# ArduinoStandaloneUsbSwitch-4Port.net
KiCad netlist of a schematic drawn in EAGLE
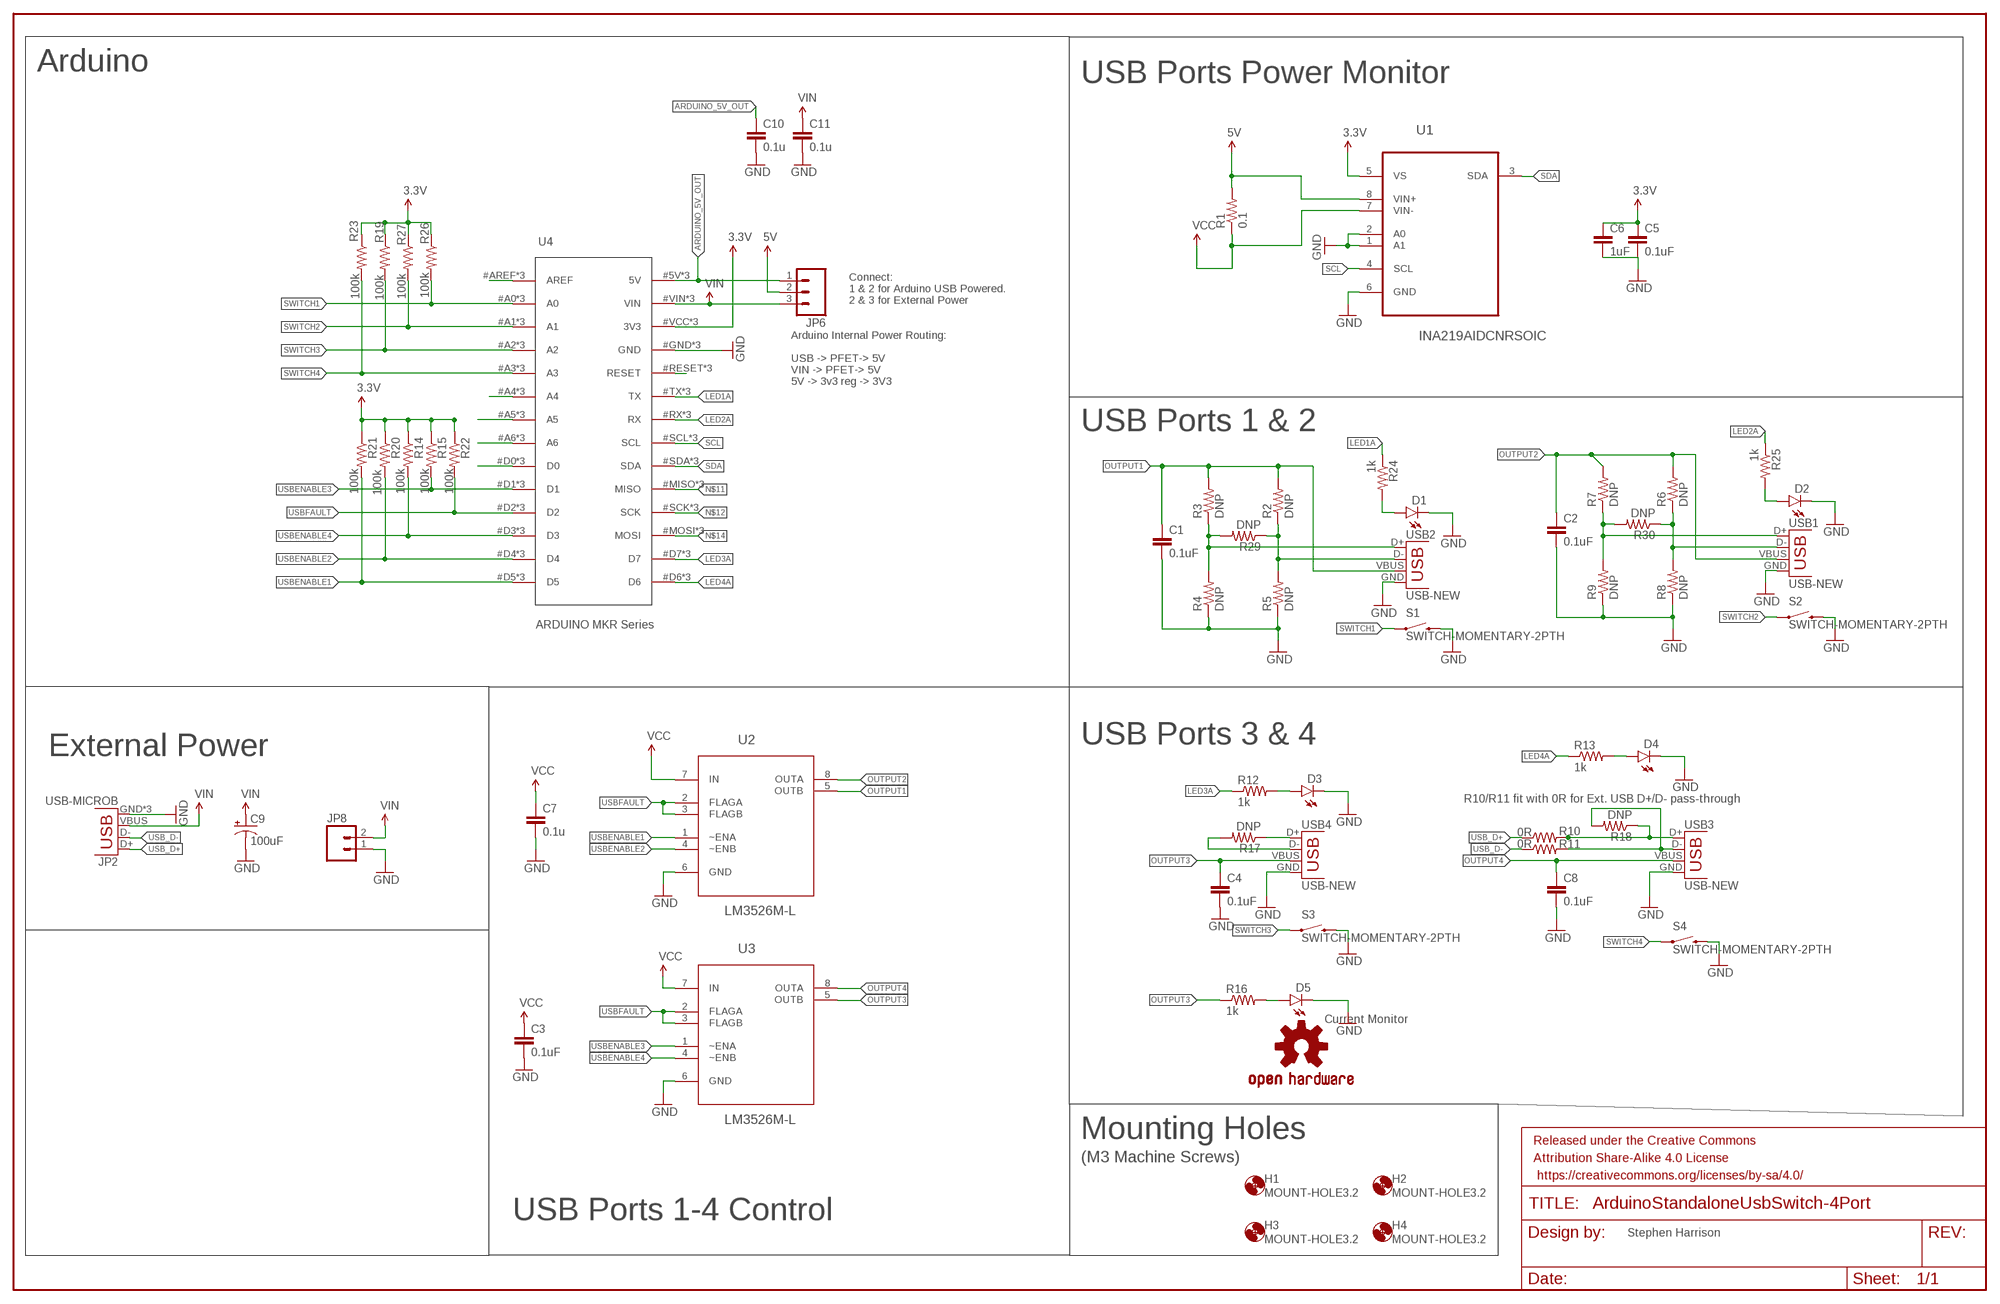
[diagram p0: schematic, sheet 1]

(export (version "E")
  (design (tool "Eeschema 10.0.6"))
  (components
    (comp (ref "C1")
      (value "0.1uF")
      (footprint "eagle-import:0805")
      (libsource (lib "eagle-import") (part "CAP0805"))
    )
    (comp (ref "C2")
      (value "0.1uF")
      (footprint "eagle-import:0805")
      (libsource (lib "eagle-import") (part "CAP0805"))
    )
    (comp (ref "C3")
      (value "0.1uF")
      (footprint "eagle-import:0805")
      (libsource (lib "eagle-import") (part "CAP0805"))
    )
    (comp (ref "C4")
      (value "0.1uF")
      (footprint "eagle-import:0805")
      (libsource (lib "eagle-import") (part "CAP0805"))
    )
    (comp (ref "C5")
      (value "0.1uF")
      (footprint "eagle-import:0805")
      (libsource (lib "eagle-import") (part "CAP0805"))
    )
    (comp (ref "C6")
      (value "1uF")
      (footprint "eagle-import:0805")
      (libsource (lib "eagle-import") (part "CAP0805"))
    )
    (comp (ref "C7")
      (value "0.1u")
      (footprint "eagle-import:0805")
      (libsource (lib "eagle-import") (part "CAP0805"))
    )
    (comp (ref "C8")
      (value "0.1uF")
      (footprint "eagle-import:0805")
      (libsource (lib "eagle-import") (part "CAP0805"))
    )
    (comp (ref "C9")
      (value "100uF")
      (footprint "eagle-import:EIA7343")
      (libsource (lib "eagle-import") (part "100UF-10V-10%(TANT)"))
    )
    (comp (ref "C10")
      (value "0.1u")
      (footprint "eagle-import:0805")
      (libsource (lib "eagle-import") (part "CAP0805"))
    )
    (comp (ref "C11")
      (value "0.1u")
      (footprint "eagle-import:0805")
      (libsource (lib "eagle-import") (part "CAP0805"))
    )
    (comp (ref "D1")
      (value "LED3MM")
      (footprint "eagle-import:LED3MM")
      (libsource (lib "eagle-import") (part "LED3MM"))
    )
    (comp (ref "D2")
      (value "LED3MM")
      (footprint "eagle-import:LED3MM")
      (libsource (lib "eagle-import") (part "LED3MM"))
    )
    (comp (ref "D3")
      (value "LED3MM")
      (footprint "eagle-import:LED3MM")
      (libsource (lib "eagle-import") (part "LED3MM"))
    )
    (comp (ref "D4")
      (value "LED3MM")
      (footprint "eagle-import:LED3MM")
      (libsource (lib "eagle-import") (part "LED3MM"))
    )
    (comp (ref "D5")
      (value "LED1206-BOTTOM")
      (footprint "eagle-import:LED-1206-BOTTOM")
      (libsource (lib "eagle-import") (part "LED1206-BOTTOM"))
    )
    (comp (ref "FRAME1")
      (value "FRAME-LEDGER")
      (footprint "eagle-import:CREATIVE_COMMONS")
      (libsource (lib "eagle-import") (part "FRAME-LEDGER"))
    )
    (comp (ref "H1")
      (value "MOUNT-HOLE3.2")
      (footprint "eagle-import:3,2")
      (libsource (lib "eagle-import") (part "MOUNT-HOLE3.2"))
    )
    (comp (ref "H2")
      (value "MOUNT-HOLE3.2")
      (footprint "eagle-import:3,2")
      (libsource (lib "eagle-import") (part "MOUNT-HOLE3.2"))
    )
    (comp (ref "H3")
      (value "MOUNT-HOLE3.2")
      (footprint "eagle-import:3,2")
      (libsource (lib "eagle-import") (part "MOUNT-HOLE3.2"))
    )
    (comp (ref "H4")
      (value "MOUNT-HOLE3.2")
      (footprint "eagle-import:3,2")
      (libsource (lib "eagle-import") (part "MOUNT-HOLE3.2"))
    )
    (comp (ref "JP2")
      (value "USB-MICROB")
      (footprint "eagle-import:USB-MICROB")
      (libsource (lib "eagle-import") (part "USB-MICROB"))
    )
    (comp (ref "JP6")
      (value "M03PTH")
      (footprint "eagle-import:1X03")
      (libsource (lib "eagle-import") (part "M03PTH"))
    )
    (comp (ref "JP8")
      (value "M025MM")
      (footprint "eagle-import:SCREWTERMINAL-5MM-2")
      (libsource (lib "eagle-import") (part "M025MM"))
    )
    (comp (ref "LOGO1")
      (value "OSHW-LOGOL")
      (footprint "eagle-import:OSHW-LOGO-L")
      (libsource (lib "eagle-import") (part "OSHW-LOGOL"))
    )
    (comp (ref "R1")
      (value "0.1")
      (footprint "eagle-import:2512")
      (libsource (lib "eagle-import") (part "0.001OHM-3W-1%(2512)3W/1%"))
    )
    (comp (ref "R2")
      (value "DNP")
      (footprint "eagle-import:0805")
      (libsource (lib "eagle-import") (part "RESISTOR0805-RES"))
    )
    (comp (ref "R3")
      (value "DNP")
      (footprint "eagle-import:0805")
      (libsource (lib "eagle-import") (part "RESISTOR0805-RES"))
    )
    (comp (ref "R4")
      (value "DNP")
      (footprint "eagle-import:0805")
      (libsource (lib "eagle-import") (part "RESISTOR0805-RES"))
    )
    (comp (ref "R5")
      (value "DNP")
      (footprint "eagle-import:0805")
      (libsource (lib "eagle-import") (part "RESISTOR0805-RES"))
    )
    (comp (ref "R6")
      (value "DNP")
      (footprint "eagle-import:0805")
      (libsource (lib "eagle-import") (part "RESISTOR0805-RES"))
    )
    (comp (ref "R7")
      (value "DNP")
      (footprint "eagle-import:0805")
      (libsource (lib "eagle-import") (part "RESISTOR0805-RES"))
    )
    (comp (ref "R8")
      (value "DNP")
      (footprint "eagle-import:0805")
      (libsource (lib "eagle-import") (part "RESISTOR0805-RES"))
    )
    (comp (ref "R9")
      (value "DNP")
      (footprint "eagle-import:0805")
      (libsource (lib "eagle-import") (part "RESISTOR0805-RES"))
    )
    (comp (ref "R10")
      (value "0R")
      (footprint "eagle-import:0805")
      (libsource (lib "eagle-import") (part "RESISTOR0805-RES"))
    )
    (comp (ref "R11")
      (value "0R")
      (footprint "eagle-import:0805")
      (libsource (lib "eagle-import") (part "RESISTOR0805-RES"))
    )
    (comp (ref "R12")
      (value "1k")
      (footprint "eagle-import:0805")
      (libsource (lib "eagle-import") (part "RESISTOR0805-RES"))
    )
    (comp (ref "R13")
      (value "1k")
      (footprint "eagle-import:0805")
      (libsource (lib "eagle-import") (part "RESISTOR0805-RES"))
    )
    (comp (ref "R14")
      (value "100k")
      (footprint "eagle-import:0805")
      (libsource (lib "eagle-import") (part "RESISTOR0805-RES"))
    )
    (comp (ref "R15")
      (value "100k")
      (footprint "eagle-import:0805")
      (libsource (lib "eagle-import") (part "RESISTOR0805-RES"))
    )
    (comp (ref "R16")
      (value "1k")
      (footprint "eagle-import:0805")
      (libsource (lib "eagle-import") (part "RESISTOR0805-RES"))
    )
    (comp (ref "R17")
      (value "DNP")
      (footprint "eagle-import:0805")
      (libsource (lib "eagle-import") (part "RESISTOR0805-RES"))
    )
    (comp (ref "R18")
      (value "DNP")
      (footprint "eagle-import:0805")
      (libsource (lib "eagle-import") (part "RESISTOR0805-RES"))
    )
    (comp (ref "R19")
      (value "100k")
      (footprint "eagle-import:0805")
      (libsource (lib "eagle-import") (part "RESISTOR0805-RES"))
    )
    (comp (ref "R20")
      (value "100k")
      (footprint "eagle-import:0805")
      (libsource (lib "eagle-import") (part "RESISTOR0805-RES"))
    )
    (comp (ref "R21")
      (value "100k")
      (footprint "eagle-import:0805")
      (libsource (lib "eagle-import") (part "RESISTOR0805-RES"))
    )
    (comp (ref "R22")
      (value "100k")
      (footprint "eagle-import:0805")
      (libsource (lib "eagle-import") (part "RESISTOR0805-RES"))
    )
    (comp (ref "R23")
      (value "100k")
      (footprint "eagle-import:0805")
      (libsource (lib "eagle-import") (part "RESISTOR0805-RES"))
    )
    (comp (ref "R24")
      (value "1k")
      (footprint "eagle-import:0805")
      (libsource (lib "eagle-import") (part "RESISTOR0805-RES"))
    )
    (comp (ref "R25")
      (value "1k")
      (footprint "eagle-import:0805")
      (libsource (lib "eagle-import") (part "RESISTOR0805-RES"))
    )
    (comp (ref "R26")
      (value "100k")
      (footprint "eagle-import:0805")
      (libsource (lib "eagle-import") (part "RESISTOR0805-RES"))
    )
    (comp (ref "R27")
      (value "100k")
      (footprint "eagle-import:0805")
      (libsource (lib "eagle-import") (part "RESISTOR0805-RES"))
    )
    (comp (ref "R29")
      (value "DNP")
      (footprint "eagle-import:0805")
      (libsource (lib "eagle-import") (part "RESISTOR0805-RES"))
    )
    (comp (ref "R30")
      (value "DNP")
      (footprint "eagle-import:0805")
      (libsource (lib "eagle-import") (part "RESISTOR0805-RES"))
    )
    (comp (ref "S1")
      (value "SWITCH-MOMENTARY-2PTH")
      (footprint "eagle-import:TACTILE-PTH")
      (libsource (lib "eagle-import") (part "SWITCH-MOMENTARY-2PTH"))
    )
    (comp (ref "S2")
      (value "SWITCH-MOMENTARY-2PTH")
      (footprint "eagle-import:TACTILE-PTH")
      (libsource (lib "eagle-import") (part "SWITCH-MOMENTARY-2PTH"))
    )
    (comp (ref "S3")
      (value "SWITCH-MOMENTARY-2PTH")
      (footprint "eagle-import:TACTILE-PTH")
      (libsource (lib "eagle-import") (part "SWITCH-MOMENTARY-2PTH"))
    )
    (comp (ref "S4")
      (value "SWITCH-MOMENTARY-2PTH")
      (footprint "eagle-import:TACTILE-PTH")
      (libsource (lib "eagle-import") (part "SWITCH-MOMENTARY-2PTH"))
    )
    (comp (ref "U1")
      (value "INA219AIDCNRSOIC")
      (footprint "eagle-import:SO08")
      (libsource (lib "eagle-import") (part "INA219AIDCNRSOIC"))
    )
    (comp (ref "U2")
      (value "LM3526M-L")
      (footprint "eagle-import:SOIC127P640X175-8N")
      (libsource (lib "eagle-import") (part "LM3526M-L"))
    )
    (comp (ref "U3")
      (value "LM3526M-L")
      (footprint "eagle-import:SOIC127P640X175-8N")
      (libsource (lib "eagle-import") (part "LM3526M-L"))
    )
    (comp (ref "U4")
      (value "ARDUINO MKR Series")
      (footprint "eagle-import:ARDUINO_MKRFOX1200_PROTOPADS")
      (libsource (lib "eagle-import") (part "ARDUINO_MKRFOX1200PROTOPADS"))
    )
    (comp (ref "USB1")
      (value "USB-NEW")
      (footprint "eagle-import:USB-A-VERTICAL")
      (libsource (lib "eagle-import") (part "USB-NEW"))
    )
    (comp (ref "USB2")
      (value "USB-NEW")
      (footprint "eagle-import:USB-A-VERTICAL")
      (libsource (lib "eagle-import") (part "USB-NEW"))
    )
    (comp (ref "USB3")
      (value "USB-NEW")
      (footprint "eagle-import:USB-A-VERTICAL")
      (libsource (lib "eagle-import") (part "USB-NEW"))
    )
    (comp (ref "USB4")
      (value "USB-NEW")
      (footprint "eagle-import:USB-A-VERTICAL")
      (libsource (lib "eagle-import") (part "USB-NEW"))
    )
  )
  (nets
    (net (code "1") (name "3.3V") (class "Default")
      (node (ref "C5") (pin "1") (pinfunction "1_1") (pintype "passive"))
      (node (ref "C6") (pin "1") (pinfunction "1_1") (pintype "passive"))
      (node (ref "R14") (pin "1") (pinfunction "1_1") (pintype "passive"))
      (node (ref "R15") (pin "1") (pinfunction "1_1") (pintype "passive"))
      (node (ref "R19") (pin "1") (pinfunction "1_1") (pintype "passive"))
      (node (ref "R20") (pin "1") (pinfunction "1_1") (pintype "passive"))
      (node (ref "R21") (pin "1") (pinfunction "1_1") (pintype "passive"))
      (node (ref "R22") (pin "1") (pinfunction "1_1") (pintype "passive"))
      (node (ref "R23") (pin "1") (pinfunction "1_1") (pintype "passive"))
      (node (ref "R26") (pin "1") (pinfunction "1_1") (pintype "passive"))
      (node (ref "R27") (pin "1") (pinfunction "1_1") (pintype "passive"))
      (node (ref "U1") (pin "5") (pinfunction "VS_5") (pintype "power_in"))
      (node (ref "U4") (pin "#VCC") (pinfunction "3V3_#VCC") (pintype "output"))
      (node (ref "U4") (pin "@VCC") (pinfunction "3V3_@VCC") (pintype "output"))
      (node (ref "U4") (pin "VCC") (pinfunction "3V3_VCC") (pintype "output"))
    )
    (net (code "2") (name "5V") (class "Default")
      (node (ref "JP6") (pin "2") (pinfunction "2_2") (pintype "passive"))
      (node (ref "R1") (pin "2") (pinfunction "2_2") (pintype "passive"))
      (node (ref "U1") (pin "8") (pinfunction "VIN+_8") (pintype "input"))
    )
    (net (code "3") (name "ARDUINO_5V_OUT") (class "Default")
      (node (ref "C10") (pin "1") (pinfunction "1_1") (pintype "passive"))
      (node (ref "JP6") (pin "1") (pinfunction "1_1") (pintype "passive"))
      (node (ref "U4") (pin "#5V") (pinfunction "5V_#5V") (pintype "output"))
      (node (ref "U4") (pin "5V") (pinfunction "5V_5V") (pintype "output"))
      (node (ref "U4") (pin "@5V") (pinfunction "5V_@5V") (pintype "output"))
    )
    (net (code "4") (name "GND") (class "Default")
      (node (ref "C1") (pin "2") (pinfunction "2_2") (pintype "passive"))
      (node (ref "C10") (pin "2") (pinfunction "2_2") (pintype "passive"))
      (node (ref "C11") (pin "2") (pinfunction "2_2") (pintype "passive"))
      (node (ref "C2") (pin "2") (pinfunction "2_2") (pintype "passive"))
      (node (ref "C3") (pin "2") (pinfunction "2_2") (pintype "passive"))
      (node (ref "C4") (pin "2") (pinfunction "2_2") (pintype "passive"))
      (node (ref "C5") (pin "2") (pinfunction "2_2") (pintype "passive"))
      (node (ref "C6") (pin "2") (pinfunction "2_2") (pintype "passive"))
      (node (ref "C7") (pin "2") (pinfunction "2_2") (pintype "passive"))
      (node (ref "C8") (pin "2") (pinfunction "2_2") (pintype "passive"))
      (node (ref "C9") (pin "C") (pinfunction "-_C") (pintype "passive"))
      (node (ref "D1") (pin "K") (pinfunction "C_K") (pintype "passive"))
      (node (ref "D2") (pin "K") (pinfunction "C_K") (pintype "passive"))
      (node (ref "D3") (pin "K") (pinfunction "C_K") (pintype "passive"))
      (node (ref "D4") (pin "K") (pinfunction "C_K") (pintype "passive"))
      (node (ref "D5") (pin "C") (pinfunction "C_C") (pintype "passive"))
      (node (ref "JP2") (pin "GND") (pinfunction "GND_GND") (pintype "bidirectional"))
      (node (ref "JP2") (pin "MT1") (pinfunction "GND_MT1") (pintype "bidirectional"))
      (node (ref "JP2") (pin "MT2") (pinfunction "GND_MT2") (pintype "bidirectional"))
      (node (ref "JP8") (pin "1") (pinfunction "1_1") (pintype "passive"))
      (node (ref "R4") (pin "1") (pinfunction "1_1") (pintype "passive"))
      (node (ref "R5") (pin "1") (pinfunction "1_1") (pintype "passive"))
      (node (ref "R8") (pin "1") (pinfunction "1_1") (pintype "passive"))
      (node (ref "R9") (pin "1") (pinfunction "1_1") (pintype "passive"))
      (node (ref "S1") (pin "3") (pinfunction "2_3") (pintype "passive"))
      (node (ref "S2") (pin "3") (pinfunction "2_3") (pintype "passive"))
      (node (ref "S3") (pin "3") (pinfunction "2_3") (pintype "passive"))
      (node (ref "S4") (pin "3") (pinfunction "2_3") (pintype "passive"))
      (node (ref "U1") (pin "1") (pinfunction "A1_1") (pintype "input"))
      (node (ref "U1") (pin "2") (pinfunction "A0_2") (pintype "input"))
      (node (ref "U1") (pin "6") (pinfunction "GND_6") (pintype "passive"))
      (node (ref "U2") (pin "6") (pinfunction "GND_6") (pintype "passive"))
      (node (ref "U3") (pin "6") (pinfunction "GND_6") (pintype "passive"))
      (node (ref "U4") (pin "#GND") (pinfunction "GND_#GND") (pintype "power_in"))
      (node (ref "U4") (pin "@GND") (pinfunction "GND_@GND") (pintype "power_in"))
      (node (ref "U4") (pin "GND") (pinfunction "GND_GND") (pintype "power_in"))
      (node (ref "USB1") (pin "GND") (pinfunction "GND_GND") (pintype "bidirectional"))
      (node (ref "USB2") (pin "GND") (pinfunction "GND_GND") (pintype "bidirectional"))
      (node (ref "USB3") (pin "GND") (pinfunction "GND_GND") (pintype "bidirectional"))
      (node (ref "USB4") (pin "GND") (pinfunction "GND_GND") (pintype "bidirectional"))
    )
    (net (code "5") (name "LED1A") (class "Default")
      (node (ref "R24") (pin "1") (pinfunction "1_1") (pintype "passive"))
      (node (ref "U4") (pin "#TX") (pinfunction "TX_#TX") (pintype "bidirectional"))
      (node (ref "U4") (pin "@TX") (pinfunction "TX_@TX") (pintype "bidirectional"))
      (node (ref "U4") (pin "TX") (pinfunction "TX_TX") (pintype "bidirectional"))
    )
    (net (code "6") (name "LED2A") (class "Default")
      (node (ref "R25") (pin "1") (pinfunction "1_1") (pintype "passive"))
      (node (ref "U4") (pin "#RX") (pinfunction "RX_#RX") (pintype "bidirectional"))
      (node (ref "U4") (pin "@RX") (pinfunction "RX_@RX") (pintype "bidirectional"))
      (node (ref "U4") (pin "RX") (pinfunction "RX_RX") (pintype "bidirectional"))
    )
    (net (code "7") (name "LED3A") (class "Default")
      (node (ref "R12") (pin "1") (pinfunction "1_1") (pintype "passive"))
      (node (ref "U4") (pin "#D7") (pinfunction "D7_#D7") (pintype "bidirectional"))
      (node (ref "U4") (pin "@D7") (pinfunction "D7_@D7") (pintype "bidirectional"))
      (node (ref "U4") (pin "D7") (pinfunction "D7_D7") (pintype "bidirectional"))
    )
    (net (code "8") (name "LED4A") (class "Default")
      (node (ref "R13") (pin "1") (pinfunction "1_1") (pintype "passive"))
      (node (ref "U4") (pin "#D6") (pinfunction "D6_#D6") (pintype "bidirectional"))
      (node (ref "U4") (pin "@D6") (pinfunction "D6_@D6") (pintype "bidirectional"))
      (node (ref "U4") (pin "D6") (pinfunction "D6_D6") (pintype "bidirectional"))
    )
    (net (code "9") (name "N$11") (class "Default")
      (node (ref "U4") (pin "#MISO") (pinfunction "MISO_#MISO") (pintype "bidirectional"))
      (node (ref "U4") (pin "@MISO") (pinfunction "MISO_@MISO") (pintype "bidirectional"))
      (node (ref "U4") (pin "MISO") (pinfunction "MISO_MISO") (pintype "bidirectional"))
    )
    (net (code "10") (name "N$12") (class "Default")
      (node (ref "U4") (pin "#SCK") (pinfunction "SCK_#SCK") (pintype "bidirectional"))
      (node (ref "U4") (pin "@SCK") (pinfunction "SCK_@SCK") (pintype "bidirectional"))
      (node (ref "U4") (pin "SCK") (pinfunction "SCK_SCK") (pintype "bidirectional"))
    )
    (net (code "11") (name "N$14") (class "Default")
      (node (ref "U4") (pin "#MOSI") (pinfunction "MOSI_#MOSI") (pintype "bidirectional"))
      (node (ref "U4") (pin "@MOSI") (pinfunction "MOSI_@MOSI") (pintype "bidirectional"))
      (node (ref "U4") (pin "MOSI") (pinfunction "MOSI_MOSI") (pintype "bidirectional"))
    )
    (net (code "12") (name "Net-(D1-PadA)") (class "Default")
      (node (ref "D1") (pin "A") (pinfunction "A_A") (pintype "passive"))
      (node (ref "R24") (pin "2") (pinfunction "2_2") (pintype "passive"))
    )
    (net (code "13") (name "Net-(D2-PadA)") (class "Default")
      (node (ref "D2") (pin "A") (pinfunction "A_A") (pintype "passive"))
      (node (ref "R25") (pin "2") (pinfunction "2_2") (pintype "passive"))
    )
    (net (code "14") (name "Net-(D3-PadA)") (class "Default")
      (node (ref "D3") (pin "A") (pinfunction "A_A") (pintype "passive"))
      (node (ref "R12") (pin "2") (pinfunction "2_2") (pintype "passive"))
    )
    (net (code "15") (name "Net-(D4-PadA)") (class "Default")
      (node (ref "D4") (pin "A") (pinfunction "A_A") (pintype "passive"))
      (node (ref "R13") (pin "2") (pinfunction "2_2") (pintype "passive"))
    )
    (net (code "16") (name "Net-(D5-PadA)") (class "Default")
      (node (ref "D5") (pin "A") (pinfunction "A_A") (pintype "passive"))
      (node (ref "R16") (pin "2") (pinfunction "2_2") (pintype "passive"))
    )
    (net (code "17") (name "Net-(R2-Pad1)") (class "Default")
      (node (ref "R2") (pin "1") (pinfunction "1_1") (pintype "passive"))
      (node (ref "R29") (pin "1") (pinfunction "1_1") (pintype "passive"))
      (node (ref "R5") (pin "2") (pinfunction "2_2") (pintype "passive"))
      (node (ref "USB2") (pin "D-") (pinfunction "D-_D-") (pintype "bidirectional"))
    )
    (net (code "18") (name "Net-(R10-Pad2)") (class "Default")
      (node (ref "R10") (pin "2") (pinfunction "2_2") (pintype "passive"))
      (node (ref "R18") (pin "1") (pinfunction "1_1") (pintype "passive"))
      (node (ref "USB3") (pin "D+") (pinfunction "D+_D+") (pintype "bidirectional"))
    )
    (net (code "19") (name "Net-(R11-Pad2)") (class "Default")
      (node (ref "R11") (pin "2") (pinfunction "2_2") (pintype "passive"))
      (node (ref "R18") (pin "2") (pinfunction "2_2") (pintype "passive"))
      (node (ref "USB3") (pin "D-") (pinfunction "D-_D-") (pintype "bidirectional"))
    )
    (net (code "20") (name "Net-(R17-Pad1)") (class "Default")
      (node (ref "R17") (pin "1") (pinfunction "1_1") (pintype "passive"))
      (node (ref "USB4") (pin "D+") (pinfunction "D+_D+") (pintype "bidirectional"))
    )
    (net (code "21") (name "Net-(R17-Pad2)") (class "Default")
      (node (ref "R17") (pin "2") (pinfunction "2_2") (pintype "passive"))
      (node (ref "USB4") (pin "D-") (pinfunction "D-_D-") (pintype "bidirectional"))
    )
    (net (code "22") (name "Net-(R29-Pad2)") (class "Default")
      (node (ref "R29") (pin "2") (pinfunction "2_2") (pintype "passive"))
      (node (ref "R3") (pin "1") (pinfunction "1_1") (pintype "passive"))
      (node (ref "R4") (pin "2") (pinfunction "2_2") (pintype "passive"))
      (node (ref "USB2") (pin "D+") (pinfunction "D+_D+") (pintype "bidirectional"))
    )
    (net (code "23") (name "Net-(R30-Pad1)") (class "Default")
      (node (ref "R30") (pin "1") (pinfunction "1_1") (pintype "passive"))
      (node (ref "R6") (pin "1") (pinfunction "1_1") (pintype "passive"))
      (node (ref "R8") (pin "2") (pinfunction "2_2") (pintype "passive"))
      (node (ref "USB1") (pin "D-") (pinfunction "D-_D-") (pintype "bidirectional"))
    )
    (net (code "24") (name "Net-(R30-Pad2)") (class "Default")
      (node (ref "R30") (pin "2") (pinfunction "2_2") (pintype "passive"))
      (node (ref "R7") (pin "1") (pinfunction "1_1") (pintype "passive"))
      (node (ref "R9") (pin "2") (pinfunction "2_2") (pintype "passive"))
      (node (ref "USB1") (pin "D+") (pinfunction "D+_D+") (pintype "bidirectional"))
    )
    (net (code "25") (name "Net-(U4-A4-Pad#A4)") (class "Default")
      (node (ref "U4") (pin "#A4") (pinfunction "A4_#A4") (pintype "bidirectional"))
      (node (ref "U4") (pin "@A4") (pinfunction "A4_@A4") (pintype "bidirectional"))
      (node (ref "U4") (pin "A4") (pinfunction "A4_A4") (pintype "bidirectional"))
    )
    (net (code "26") (name "Net-(U4-A5-Pad#A5)") (class "Default")
      (node (ref "U4") (pin "#A5") (pinfunction "A5_#A5") (pintype "bidirectional"))
      (node (ref "U4") (pin "@A5") (pinfunction "A5_@A5") (pintype "bidirectional"))
      (node (ref "U4") (pin "A5") (pinfunction "A5_A5") (pintype "bidirectional"))
    )
    (net (code "27") (name "Net-(U4-A6-Pad#A6)") (class "Default")
      (node (ref "U4") (pin "#A6") (pinfunction "A6_#A6") (pintype "bidirectional"))
      (node (ref "U4") (pin "@A6") (pinfunction "A6_@A6") (pintype "bidirectional"))
      (node (ref "U4") (pin "A6") (pinfunction "A6_A6") (pintype "bidirectional"))
    )
    (net (code "28") (name "Net-(U4-AREF-Pad#AREF)") (class "Default")
      (node (ref "U4") (pin "#AREF") (pinfunction "AREF_#AREF") (pintype "bidirectional"))
      (node (ref "U4") (pin "@AREF") (pinfunction "AREF_@AREF") (pintype "bidirectional"))
      (node (ref "U4") (pin "AREF") (pinfunction "AREF_AREF") (pintype "bidirectional"))
    )
    (net (code "29") (name "Net-(U4-D0-Pad#D0)") (class "Default")
      (node (ref "U4") (pin "#D0") (pinfunction "D0_#D0") (pintype "bidirectional"))
      (node (ref "U4") (pin "@D0") (pinfunction "D0_@D0") (pintype "bidirectional"))
      (node (ref "U4") (pin "D0") (pinfunction "D0_D0") (pintype "bidirectional"))
    )
    (net (code "30") (name "Net-(U4-PadRESET)") (class "Default")
      (node (ref "U4") (pin "#RESET") (pinfunction "RESET_#RESET") (pintype "bidirectional"))
      (node (ref "U4") (pin "@RESET") (pinfunction "RESET_@RESET") (pintype "bidirectional"))
      (node (ref "U4") (pin "RESET") (pinfunction "RESET_RESET") (pintype "bidirectional"))
    )
    (net (code "31") (name "OUTPUT1") (class "Default")
      (node (ref "C1") (pin "1") (pinfunction "1_1") (pintype "passive"))
      (node (ref "R2") (pin "2") (pinfunction "2_2") (pintype "passive"))
      (node (ref "R3") (pin "2") (pinfunction "2_2") (pintype "passive"))
      (node (ref "U2") (pin "5") (pinfunction "OUTB_5") (pintype "output"))
      (node (ref "USB2") (pin "VBUS") (pinfunction "VBUS_VBUS") (pintype "bidirectional"))
    )
    (net (code "32") (name "OUTPUT2") (class "Default")
      (node (ref "C2") (pin "1") (pinfunction "1_1") (pintype "passive"))
      (node (ref "R6") (pin "2") (pinfunction "2_2") (pintype "passive"))
      (node (ref "R7") (pin "2") (pinfunction "2_2") (pintype "passive"))
      (node (ref "U2") (pin "8") (pinfunction "OUTA_8") (pintype "output"))
      (node (ref "USB1") (pin "VBUS") (pinfunction "VBUS_VBUS") (pintype "bidirectional"))
    )
    (net (code "33") (name "OUTPUT3") (class "Default")
      (node (ref "C4") (pin "1") (pinfunction "1_1") (pintype "passive"))
      (node (ref "R16") (pin "1") (pinfunction "1_1") (pintype "passive"))
      (node (ref "U3") (pin "5") (pinfunction "OUTB_5") (pintype "output"))
      (node (ref "USB4") (pin "VBUS") (pinfunction "VBUS_VBUS") (pintype "bidirectional"))
    )
    (net (code "34") (name "OUTPUT4") (class "Default")
      (node (ref "C8") (pin "1") (pinfunction "1_1") (pintype "passive"))
      (node (ref "U3") (pin "8") (pinfunction "OUTA_8") (pintype "output"))
      (node (ref "USB3") (pin "VBUS") (pinfunction "VBUS_VBUS") (pintype "bidirectional"))
    )
    (net (code "35") (name "SCL") (class "Default")
      (node (ref "U1") (pin "4") (pinfunction "SCL_4") (pintype "input"))
      (node (ref "U4") (pin "#SCL") (pinfunction "SCL_#SCL") (pintype "bidirectional"))
      (node (ref "U4") (pin "@SCL") (pinfunction "SCL_@SCL") (pintype "bidirectional"))
      (node (ref "U4") (pin "SCL") (pinfunction "SCL_SCL") (pintype "bidirectional"))
    )
    (net (code "36") (name "SDA") (class "Default")
      (node (ref "U1") (pin "3") (pinfunction "SDA_3") (pintype "bidirectional"))
      (node (ref "U4") (pin "#SDA") (pinfunction "SDA_#SDA") (pintype "bidirectional"))
      (node (ref "U4") (pin "@SDA") (pinfunction "SDA_@SDA") (pintype "bidirectional"))
      (node (ref "U4") (pin "SDA") (pinfunction "SDA_SDA") (pintype "bidirectional"))
    )
    (net (code "37") (name "SWITCH1") (class "Default")
      (node (ref "R26") (pin "2") (pinfunction "2_2") (pintype "passive"))
      (node (ref "S1") (pin "1") (pinfunction "1_1") (pintype "passive"))
      (node (ref "U4") (pin "#A0") (pinfunction "A0_#A0") (pintype "bidirectional"))
      (node (ref "U4") (pin "@A0") (pinfunction "A0_@A0") (pintype "bidirectional"))
      (node (ref "U4") (pin "A0") (pinfunction "A0_A0") (pintype "bidirectional"))
    )
    (net (code "38") (name "SWITCH2") (class "Default")
      (node (ref "R27") (pin "2") (pinfunction "2_2") (pintype "passive"))
      (node (ref "S2") (pin "1") (pinfunction "1_1") (pintype "passive"))
      (node (ref "U4") (pin "#A1") (pinfunction "A1_#A1") (pintype "bidirectional"))
      (node (ref "U4") (pin "@A1") (pinfunction "A1_@A1") (pintype "bidirectional"))
      (node (ref "U4") (pin "A1") (pinfunction "A1_A1") (pintype "bidirectional"))
    )
    (net (code "39") (name "SWITCH3") (class "Default")
      (node (ref "R19") (pin "2") (pinfunction "2_2") (pintype "passive"))
      (node (ref "S3") (pin "1") (pinfunction "1_1") (pintype "passive"))
      (node (ref "U4") (pin "#A2") (pinfunction "A2_#A2") (pintype "bidirectional"))
      (node (ref "U4") (pin "@A2") (pinfunction "A2_@A2") (pintype "bidirectional"))
      (node (ref "U4") (pin "A2") (pinfunction "A2_A2") (pintype "bidirectional"))
    )
    (net (code "40") (name "SWITCH4") (class "Default")
      (node (ref "R23") (pin "2") (pinfunction "2_2") (pintype "passive"))
      (node (ref "S4") (pin "1") (pinfunction "1_1") (pintype "passive"))
      (node (ref "U4") (pin "#A3") (pinfunction "A3_#A3") (pintype "bidirectional"))
      (node (ref "U4") (pin "@A3") (pinfunction "A3_@A3") (pintype "bidirectional"))
      (node (ref "U4") (pin "A3") (pinfunction "A3_A3") (pintype "bidirectional"))
    )
    (net (code "41") (name "USBENABLE1") (class "Default")
      (node (ref "R21") (pin "2") (pinfunction "2_2") (pintype "passive"))
      (node (ref "U2") (pin "1") (pinfunction "~{ENA}_1") (pintype "input"))
      (node (ref "U4") (pin "#D5") (pinfunction "D5_#D5") (pintype "bidirectional"))
      (node (ref "U4") (pin "@D5") (pinfunction "D5_@D5") (pintype "bidirectional"))
      (node (ref "U4") (pin "D5") (pinfunction "D5_D5") (pintype "bidirectional"))
    )
    (net (code "42") (name "USBENABLE2") (class "Default")
      (node (ref "R20") (pin "2") (pinfunction "2_2") (pintype "passive"))
      (node (ref "U2") (pin "4") (pinfunction "~{ENB}_4") (pintype "input"))
      (node (ref "U4") (pin "#D4") (pinfunction "D4_#D4") (pintype "bidirectional"))
      (node (ref "U4") (pin "@D4") (pinfunction "D4_@D4") (pintype "bidirectional"))
      (node (ref "U4") (pin "D4") (pinfunction "D4_D4") (pintype "bidirectional"))
    )
    (net (code "43") (name "USBENABLE3") (class "Default")
      (node (ref "R15") (pin "2") (pinfunction "2_2") (pintype "passive"))
      (node (ref "U3") (pin "1") (pinfunction "~{ENA}_1") (pintype "input"))
      (node (ref "U4") (pin "#D1") (pinfunction "D1_#D1") (pintype "bidirectional"))
      (node (ref "U4") (pin "@D1") (pinfunction "D1_@D1") (pintype "bidirectional"))
      (node (ref "U4") (pin "D1") (pinfunction "D1_D1") (pintype "bidirectional"))
    )
    (net (code "44") (name "USBENABLE4") (class "Default")
      (node (ref "R14") (pin "2") (pinfunction "2_2") (pintype "passive"))
      (node (ref "U3") (pin "4") (pinfunction "~{ENB}_4") (pintype "input"))
      (node (ref "U4") (pin "#D3") (pinfunction "D3_#D3") (pintype "bidirectional"))
      (node (ref "U4") (pin "@D3") (pinfunction "D3_@D3") (pintype "bidirectional"))
      (node (ref "U4") (pin "D3") (pinfunction "D3_D3") (pintype "bidirectional"))
    )
    (net (code "45") (name "USBFAULT") (class "Default")
      (node (ref "R22") (pin "2") (pinfunction "2_2") (pintype "passive"))
      (node (ref "U2") (pin "2") (pinfunction "FLAGA_2") (pintype "input"))
      (node (ref "U2") (pin "3") (pinfunction "FLAGB_3") (pintype "input"))
      (node (ref "U3") (pin "2") (pinfunction "FLAGA_2") (pintype "input"))
      (node (ref "U3") (pin "3") (pinfunction "FLAGB_3") (pintype "input"))
      (node (ref "U4") (pin "#D2") (pinfunction "D2_#D2") (pintype "bidirectional"))
      (node (ref "U4") (pin "@D2") (pinfunction "D2_@D2") (pintype "bidirectional"))
      (node (ref "U4") (pin "D2") (pinfunction "D2_D2") (pintype "bidirectional"))
    )
    (net (code "46") (name "USB_D+") (class "Default")
      (node (ref "JP2") (pin "D+") (pinfunction "D+_D+") (pintype "bidirectional"))
      (node (ref "R10") (pin "1") (pinfunction "1_1") (pintype "passive"))
    )
    (net (code "47") (name "USB_D-") (class "Default")
      (node (ref "JP2") (pin "D-") (pinfunction "D-_D-") (pintype "bidirectional"))
      (node (ref "R11") (pin "1") (pinfunction "1_1") (pintype "passive"))
    )
    (net (code "48") (name "VCC") (class "Default")
      (node (ref "C3") (pin "1") (pinfunction "1_1") (pintype "passive"))
      (node (ref "C7") (pin "1") (pinfunction "1_1") (pintype "passive"))
      (node (ref "R1") (pin "1") (pinfunction "1_1") (pintype "passive"))
      (node (ref "U1") (pin "7") (pinfunction "VIN-_7") (pintype "input"))
      (node (ref "U2") (pin "7") (pinfunction "IN_7") (pintype "power_in"))
      (node (ref "U3") (pin "7") (pinfunction "IN_7") (pintype "power_in"))
    )
    (net (code "49") (name "VIN") (class "Default")
      (node (ref "C11") (pin "1") (pinfunction "1_1") (pintype "passive"))
      (node (ref "C9") (pin "A") (pinfunction "+_A") (pintype "passive"))
      (node (ref "JP2") (pin "VBUS") (pinfunction "VBUS_VBUS") (pintype "bidirectional"))
      (node (ref "JP6") (pin "3") (pinfunction "3_3") (pintype "passive"))
      (node (ref "JP8") (pin "2") (pinfunction "2_2") (pintype "passive"))
      (node (ref "U4") (pin "#VIN") (pinfunction "VIN_#VIN") (pintype "input"))
      (node (ref "U4") (pin "@VIN") (pinfunction "VIN_@VIN") (pintype "input"))
      (node (ref "U4") (pin "VIN") (pinfunction "VIN_VIN") (pintype "input"))
    )
  )
)
